# osh-2l-cpwg-via75.net
KiCad netlist of a schematic drawn in EAGLE
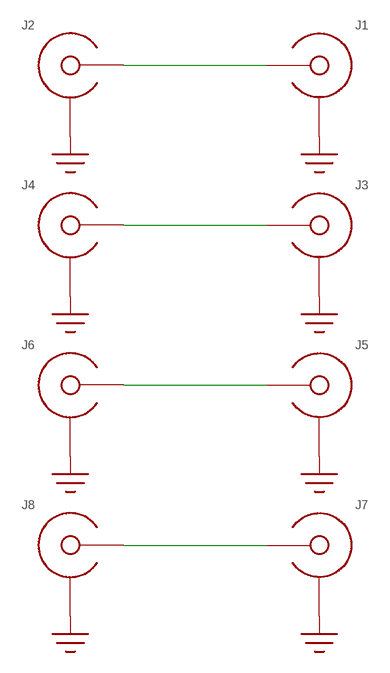
[diagram p0: schematic, sheet 1]

(export (version "E")
  (design (tool "Eeschema 10.0.6"))
  (components
    (comp (ref "J1")
      (value "SMA-EDGE-LAUNCH4020_TAPER")
      (footprint "eagle-import:SMA_EDGE_LAUNCH_2L_4020_TAPER")
      (libsource (lib "eagle-import") (part "SMA-EDGE-LAUNCH4020_TAPER"))
    )
    (comp (ref "J2")
      (value "SMA-EDGE-LAUNCHCUT-PIN")
      (footprint "eagle-import:SMA_EDGE_LAUNCH_2L_4020_CUT_PIN")
      (libsource (lib "eagle-import") (part "SMA-EDGE-LAUNCHCUT-PIN"))
    )
    (comp (ref "J3")
      (value "SMA-EDGE-LAUNCH4020_TAPER")
      (footprint "eagle-import:SMA_EDGE_LAUNCH_2L_4020_TAPER")
      (libsource (lib "eagle-import") (part "SMA-EDGE-LAUNCH4020_TAPER"))
    )
    (comp (ref "J4")
      (value "SMA-EDGE-LAUNCHCUT-PIN")
      (footprint "eagle-import:SMA_EDGE_LAUNCH_2L_4020_CUT_PIN")
      (libsource (lib "eagle-import") (part "SMA-EDGE-LAUNCHCUT-PIN"))
    )
    (comp (ref "J5")
      (value "SMA-EDGE-LAUNCH4020_TAPER")
      (footprint "eagle-import:SMA_EDGE_LAUNCH_2L_4020_TAPER")
      (libsource (lib "eagle-import") (part "SMA-EDGE-LAUNCH4020_TAPER"))
    )
    (comp (ref "J6")
      (value "SMA-EDGE-LAUNCHCUT-PIN")
      (footprint "eagle-import:SMA_EDGE_LAUNCH_2L_4020_CUT_PIN")
      (libsource (lib "eagle-import") (part "SMA-EDGE-LAUNCHCUT-PIN"))
    )
    (comp (ref "J7")
      (value "SMA-EDGE-LAUNCH4020_TAPER")
      (footprint "eagle-import:SMA_EDGE_LAUNCH_2L_4020_TAPER")
      (libsource (lib "eagle-import") (part "SMA-EDGE-LAUNCH4020_TAPER"))
    )
    (comp (ref "J8")
      (value "SMA-EDGE-LAUNCHCUT-PIN")
      (footprint "eagle-import:SMA_EDGE_LAUNCH_2L_4020_CUT_PIN")
      (libsource (lib "eagle-import") (part "SMA-EDGE-LAUNCHCUT-PIN"))
    )
  )
  (nets
    (net (code "1") (name "GND") (class "Default")
      (node (ref "J1") (pin "BOTTOM_GND") (pinfunction "SHIELD_BOTTOM_GND") (pintype "bidirectional"))
      (node (ref "J1") (pin "GND@1") (pinfunction "SHIELD_GND@1") (pintype "bidirectional"))
      (node (ref "J1") (pin "GND@14") (pinfunction "SHIELD_GND@14") (pintype "bidirectional"))
      (node (ref "J1") (pin "GND@15") (pinfunction "SHIELD_GND@15") (pintype "bidirectional"))
      (node (ref "J1") (pin "GND@16") (pinfunction "SHIELD_GND@16") (pintype "bidirectional"))
      (node (ref "J1") (pin "GND@17") (pinfunction "SHIELD_GND@17") (pintype "bidirectional"))
      (node (ref "J1") (pin "GND@2") (pinfunction "SHIELD_GND@2") (pintype "bidirectional"))
      (node (ref "J1") (pin "GND@3") (pinfunction "SHIELD_GND@3") (pintype "bidirectional"))
      (node (ref "J1") (pin "GND@4") (pinfunction "SHIELD_GND@4") (pintype "bidirectional"))
      (node (ref "J1") (pin "GND@5") (pinfunction "SHIELD_GND@5") (pintype "bidirectional"))
      (node (ref "J1") (pin "GND@6") (pinfunction "SHIELD_GND@6") (pintype "bidirectional"))
      (node (ref "J1") (pin "GND@7") (pinfunction "SHIELD_GND@7") (pintype "bidirectional"))
      (node (ref "J1") (pin "GND@8") (pinfunction "SHIELD_GND@8") (pintype "bidirectional"))
      (node (ref "J1") (pin "GND_PAD1") (pinfunction "SHIELD_GND_PAD1") (pintype "bidirectional"))
      (node (ref "J1") (pin "GND_PAD2") (pinfunction "SHIELD_GND_PAD2") (pintype "bidirectional"))
      (node (ref "J1") (pin "P$1") (pinfunction "SHIELD_P$1") (pintype "bidirectional"))
      (node (ref "J1") (pin "P$2") (pinfunction "SHIELD_P$2") (pintype "bidirectional"))
      (node (ref "J2") (pin "BOTTOM_GND") (pinfunction "SHIELD_BOTTOM_GND") (pintype "bidirectional"))
      (node (ref "J2") (pin "GND@1") (pinfunction "SHIELD_GND@1") (pintype "bidirectional"))
      (node (ref "J2") (pin "GND@14") (pinfunction "SHIELD_GND@14") (pintype "bidirectional"))
      (node (ref "J2") (pin "GND@15") (pinfunction "SHIELD_GND@15") (pintype "bidirectional"))
      (node (ref "J2") (pin "GND@16") (pinfunction "SHIELD_GND@16") (pintype "bidirectional"))
      (node (ref "J2") (pin "GND@17") (pinfunction "SHIELD_GND@17") (pintype "bidirectional"))
      (node (ref "J2") (pin "GND@2") (pinfunction "SHIELD_GND@2") (pintype "bidirectional"))
      (node (ref "J2") (pin "GND@3") (pinfunction "SHIELD_GND@3") (pintype "bidirectional"))
      (node (ref "J2") (pin "GND@4") (pinfunction "SHIELD_GND@4") (pintype "bidirectional"))
      (node (ref "J2") (pin "GND@5") (pinfunction "SHIELD_GND@5") (pintype "bidirectional"))
      (node (ref "J2") (pin "GND@6") (pinfunction "SHIELD_GND@6") (pintype "bidirectional"))
      (node (ref "J2") (pin "GND@7") (pinfunction "SHIELD_GND@7") (pintype "bidirectional"))
      (node (ref "J2") (pin "GND@8") (pinfunction "SHIELD_GND@8") (pintype "bidirectional"))
      (node (ref "J2") (pin "GND_PAD1") (pinfunction "SHIELD_GND_PAD1") (pintype "bidirectional"))
      (node (ref "J2") (pin "GND_PAD2") (pinfunction "SHIELD_GND_PAD2") (pintype "bidirectional"))
      (node (ref "J3") (pin "BOTTOM_GND") (pinfunction "SHIELD_BOTTOM_GND") (pintype "bidirectional"))
      (node (ref "J3") (pin "GND@1") (pinfunction "SHIELD_GND@1") (pintype "bidirectional"))
      (node (ref "J3") (pin "GND@14") (pinfunction "SHIELD_GND@14") (pintype "bidirectional"))
      (node (ref "J3") (pin "GND@15") (pinfunction "SHIELD_GND@15") (pintype "bidirectional"))
      (node (ref "J3") (pin "GND@16") (pinfunction "SHIELD_GND@16") (pintype "bidirectional"))
      (node (ref "J3") (pin "GND@17") (pinfunction "SHIELD_GND@17") (pintype "bidirectional"))
      (node (ref "J3") (pin "GND@2") (pinfunction "SHIELD_GND@2") (pintype "bidirectional"))
      (node (ref "J3") (pin "GND@3") (pinfunction "SHIELD_GND@3") (pintype "bidirectional"))
      (node (ref "J3") (pin "GND@4") (pinfunction "SHIELD_GND@4") (pintype "bidirectional"))
      (node (ref "J3") (pin "GND@5") (pinfunction "SHIELD_GND@5") (pintype "bidirectional"))
      (node (ref "J3") (pin "GND@6") (pinfunction "SHIELD_GND@6") (pintype "bidirectional"))
      (node (ref "J3") (pin "GND@7") (pinfunction "SHIELD_GND@7") (pintype "bidirectional"))
      (node (ref "J3") (pin "GND@8") (pinfunction "SHIELD_GND@8") (pintype "bidirectional"))
      (node (ref "J3") (pin "GND_PAD1") (pinfunction "SHIELD_GND_PAD1") (pintype "bidirectional"))
      (node (ref "J3") (pin "GND_PAD2") (pinfunction "SHIELD_GND_PAD2") (pintype "bidirectional"))
      (node (ref "J3") (pin "P$1") (pinfunction "SHIELD_P$1") (pintype "bidirectional"))
      (node (ref "J3") (pin "P$2") (pinfunction "SHIELD_P$2") (pintype "bidirectional"))
      (node (ref "J4") (pin "BOTTOM_GND") (pinfunction "SHIELD_BOTTOM_GND") (pintype "bidirectional"))
      (node (ref "J4") (pin "GND@1") (pinfunction "SHIELD_GND@1") (pintype "bidirectional"))
      (node (ref "J4") (pin "GND@14") (pinfunction "SHIELD_GND@14") (pintype "bidirectional"))
      (node (ref "J4") (pin "GND@15") (pinfunction "SHIELD_GND@15") (pintype "bidirectional"))
      (node (ref "J4") (pin "GND@16") (pinfunction "SHIELD_GND@16") (pintype "bidirectional"))
      (node (ref "J4") (pin "GND@17") (pinfunction "SHIELD_GND@17") (pintype "bidirectional"))
      (node (ref "J4") (pin "GND@2") (pinfunction "SHIELD_GND@2") (pintype "bidirectional"))
      (node (ref "J4") (pin "GND@3") (pinfunction "SHIELD_GND@3") (pintype "bidirectional"))
      (node (ref "J4") (pin "GND@4") (pinfunction "SHIELD_GND@4") (pintype "bidirectional"))
      (node (ref "J4") (pin "GND@5") (pinfunction "SHIELD_GND@5") (pintype "bidirectional"))
      (node (ref "J4") (pin "GND@6") (pinfunction "SHIELD_GND@6") (pintype "bidirectional"))
      (node (ref "J4") (pin "GND@7") (pinfunction "SHIELD_GND@7") (pintype "bidirectional"))
      (node (ref "J4") (pin "GND@8") (pinfunction "SHIELD_GND@8") (pintype "bidirectional"))
      (node (ref "J4") (pin "GND_PAD1") (pinfunction "SHIELD_GND_PAD1") (pintype "bidirectional"))
      (node (ref "J4") (pin "GND_PAD2") (pinfunction "SHIELD_GND_PAD2") (pintype "bidirectional"))
      (node (ref "J5") (pin "BOTTOM_GND") (pinfunction "SHIELD_BOTTOM_GND") (pintype "bidirectional"))
      (node (ref "J5") (pin "GND@1") (pinfunction "SHIELD_GND@1") (pintype "bidirectional"))
      (node (ref "J5") (pin "GND@14") (pinfunction "SHIELD_GND@14") (pintype "bidirectional"))
      (node (ref "J5") (pin "GND@15") (pinfunction "SHIELD_GND@15") (pintype "bidirectional"))
      (node (ref "J5") (pin "GND@16") (pinfunction "SHIELD_GND@16") (pintype "bidirectional"))
      (node (ref "J5") (pin "GND@17") (pinfunction "SHIELD_GND@17") (pintype "bidirectional"))
      (node (ref "J5") (pin "GND@2") (pinfunction "SHIELD_GND@2") (pintype "bidirectional"))
      (node (ref "J5") (pin "GND@3") (pinfunction "SHIELD_GND@3") (pintype "bidirectional"))
      (node (ref "J5") (pin "GND@4") (pinfunction "SHIELD_GND@4") (pintype "bidirectional"))
      (node (ref "J5") (pin "GND@5") (pinfunction "SHIELD_GND@5") (pintype "bidirectional"))
      (node (ref "J5") (pin "GND@6") (pinfunction "SHIELD_GND@6") (pintype "bidirectional"))
      (node (ref "J5") (pin "GND@7") (pinfunction "SHIELD_GND@7") (pintype "bidirectional"))
      (node (ref "J5") (pin "GND@8") (pinfunction "SHIELD_GND@8") (pintype "bidirectional"))
      (node (ref "J5") (pin "GND_PAD1") (pinfunction "SHIELD_GND_PAD1") (pintype "bidirectional"))
      (node (ref "J5") (pin "GND_PAD2") (pinfunction "SHIELD_GND_PAD2") (pintype "bidirectional"))
      (node (ref "J5") (pin "P$1") (pinfunction "SHIELD_P$1") (pintype "bidirectional"))
      (node (ref "J5") (pin "P$2") (pinfunction "SHIELD_P$2") (pintype "bidirectional"))
      (node (ref "J6") (pin "BOTTOM_GND") (pinfunction "SHIELD_BOTTOM_GND") (pintype "bidirectional"))
      (node (ref "J6") (pin "GND@1") (pinfunction "SHIELD_GND@1") (pintype "bidirectional"))
      (node (ref "J6") (pin "GND@14") (pinfunction "SHIELD_GND@14") (pintype "bidirectional"))
      (node (ref "J6") (pin "GND@15") (pinfunction "SHIELD_GND@15") (pintype "bidirectional"))
      (node (ref "J6") (pin "GND@16") (pinfunction "SHIELD_GND@16") (pintype "bidirectional"))
      (node (ref "J6") (pin "GND@17") (pinfunction "SHIELD_GND@17") (pintype "bidirectional"))
      (node (ref "J6") (pin "GND@2") (pinfunction "SHIELD_GND@2") (pintype "bidirectional"))
      (node (ref "J6") (pin "GND@3") (pinfunction "SHIELD_GND@3") (pintype "bidirectional"))
      (node (ref "J6") (pin "GND@4") (pinfunction "SHIELD_GND@4") (pintype "bidirectional"))
      (node (ref "J6") (pin "GND@5") (pinfunction "SHIELD_GND@5") (pintype "bidirectional"))
      (node (ref "J6") (pin "GND@6") (pinfunction "SHIELD_GND@6") (pintype "bidirectional"))
      (node (ref "J6") (pin "GND@7") (pinfunction "SHIELD_GND@7") (pintype "bidirectional"))
      (node (ref "J6") (pin "GND@8") (pinfunction "SHIELD_GND@8") (pintype "bidirectional"))
      (node (ref "J6") (pin "GND_PAD1") (pinfunction "SHIELD_GND_PAD1") (pintype "bidirectional"))
      (node (ref "J6") (pin "GND_PAD2") (pinfunction "SHIELD_GND_PAD2") (pintype "bidirectional"))
      (node (ref "J7") (pin "BOTTOM_GND") (pinfunction "SHIELD_BOTTOM_GND") (pintype "bidirectional"))
      (node (ref "J7") (pin "GND@1") (pinfunction "SHIELD_GND@1") (pintype "bidirectional"))
      (node (ref "J7") (pin "GND@14") (pinfunction "SHIELD_GND@14") (pintype "bidirectional"))
      (node (ref "J7") (pin "GND@15") (pinfunction "SHIELD_GND@15") (pintype "bidirectional"))
      (node (ref "J7") (pin "GND@16") (pinfunction "SHIELD_GND@16") (pintype "bidirectional"))
      (node (ref "J7") (pin "GND@17") (pinfunction "SHIELD_GND@17") (pintype "bidirectional"))
      (node (ref "J7") (pin "GND@2") (pinfunction "SHIELD_GND@2") (pintype "bidirectional"))
      (node (ref "J7") (pin "GND@3") (pinfunction "SHIELD_GND@3") (pintype "bidirectional"))
      (node (ref "J7") (pin "GND@4") (pinfunction "SHIELD_GND@4") (pintype "bidirectional"))
      (node (ref "J7") (pin "GND@5") (pinfunction "SHIELD_GND@5") (pintype "bidirectional"))
      (node (ref "J7") (pin "GND@6") (pinfunction "SHIELD_GND@6") (pintype "bidirectional"))
      (node (ref "J7") (pin "GND@7") (pinfunction "SHIELD_GND@7") (pintype "bidirectional"))
      (node (ref "J7") (pin "GND@8") (pinfunction "SHIELD_GND@8") (pintype "bidirectional"))
      (node (ref "J7") (pin "GND_PAD1") (pinfunction "SHIELD_GND_PAD1") (pintype "bidirectional"))
      (node (ref "J7") (pin "GND_PAD2") (pinfunction "SHIELD_GND_PAD2") (pintype "bidirectional"))
      (node (ref "J7") (pin "P$1") (pinfunction "SHIELD_P$1") (pintype "bidirectional"))
      (node (ref "J7") (pin "P$2") (pinfunction "SHIELD_P$2") (pintype "bidirectional"))
      (node (ref "J8") (pin "BOTTOM_GND") (pinfunction "SHIELD_BOTTOM_GND") (pintype "bidirectional"))
      (node (ref "J8") (pin "GND@1") (pinfunction "SHIELD_GND@1") (pintype "bidirectional"))
      (node (ref "J8") (pin "GND@14") (pinfunction "SHIELD_GND@14") (pintype "bidirectional"))
      (node (ref "J8") (pin "GND@15") (pinfunction "SHIELD_GND@15") (pintype "bidirectional"))
      (node (ref "J8") (pin "GND@16") (pinfunction "SHIELD_GND@16") (pintype "bidirectional"))
      (node (ref "J8") (pin "GND@17") (pinfunction "SHIELD_GND@17") (pintype "bidirectional"))
      (node (ref "J8") (pin "GND@2") (pinfunction "SHIELD_GND@2") (pintype "bidirectional"))
      (node (ref "J8") (pin "GND@3") (pinfunction "SHIELD_GND@3") (pintype "bidirectional"))
      (node (ref "J8") (pin "GND@4") (pinfunction "SHIELD_GND@4") (pintype "bidirectional"))
      (node (ref "J8") (pin "GND@5") (pinfunction "SHIELD_GND@5") (pintype "bidirectional"))
      (node (ref "J8") (pin "GND@6") (pinfunction "SHIELD_GND@6") (pintype "bidirectional"))
      (node (ref "J8") (pin "GND@7") (pinfunction "SHIELD_GND@7") (pintype "bidirectional"))
      (node (ref "J8") (pin "GND@8") (pinfunction "SHIELD_GND@8") (pintype "bidirectional"))
      (node (ref "J8") (pin "GND_PAD1") (pinfunction "SHIELD_GND_PAD1") (pintype "bidirectional"))
      (node (ref "J8") (pin "GND_PAD2") (pinfunction "SHIELD_GND_PAD2") (pintype "bidirectional"))
    )
    (net (code "2") (name "Net-(J1-CENTER)") (class "Default")
      (node (ref "J1") (pin "CENTER@1") (pinfunction "CENTER_CENTER@1") (pintype "bidirectional"))
      (node (ref "J2") (pin "CENTER@1") (pinfunction "CENTER_CENTER@1") (pintype "bidirectional"))
      (node (ref "J2") (pin "CENTER@3") (pinfunction "CENTER_CENTER@3") (pintype "bidirectional"))
    )
    (net (code "3") (name "Net-(J3-CENTER)") (class "Default")
      (node (ref "J3") (pin "CENTER@1") (pinfunction "CENTER_CENTER@1") (pintype "bidirectional"))
      (node (ref "J4") (pin "CENTER@1") (pinfunction "CENTER_CENTER@1") (pintype "bidirectional"))
      (node (ref "J4") (pin "CENTER@3") (pinfunction "CENTER_CENTER@3") (pintype "bidirectional"))
    )
    (net (code "4") (name "Net-(J5-CENTER)") (class "Default")
      (node (ref "J5") (pin "CENTER@1") (pinfunction "CENTER_CENTER@1") (pintype "bidirectional"))
      (node (ref "J6") (pin "CENTER@1") (pinfunction "CENTER_CENTER@1") (pintype "bidirectional"))
      (node (ref "J6") (pin "CENTER@3") (pinfunction "CENTER_CENTER@3") (pintype "bidirectional"))
    )
    (net (code "5") (name "Net-(J7-CENTER)") (class "Default")
      (node (ref "J7") (pin "CENTER@1") (pinfunction "CENTER_CENTER@1") (pintype "bidirectional"))
      (node (ref "J8") (pin "CENTER@1") (pinfunction "CENTER_CENTER@1") (pintype "bidirectional"))
      (node (ref "J8") (pin "CENTER@3") (pinfunction "CENTER_CENTER@3") (pintype "bidirectional"))
    )
  )
)
